# LNA.net
KiCad netlist of a schematic drawn in Altium Designer
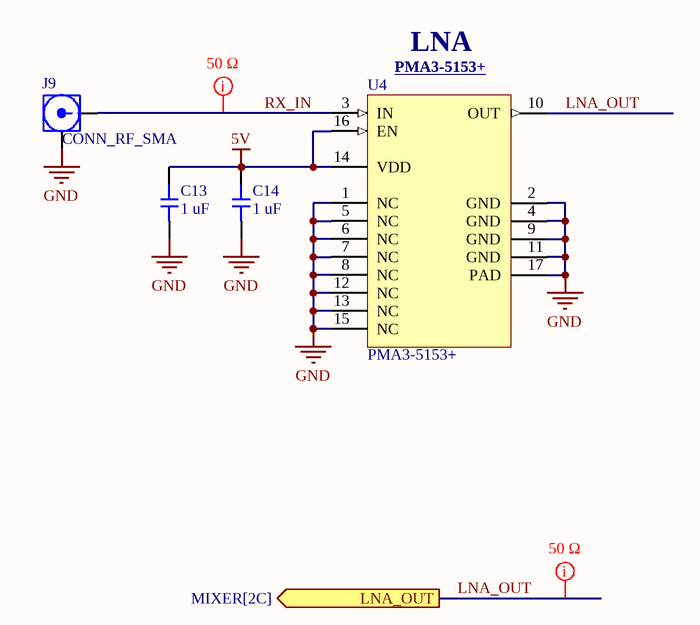
[diagram p0: LNA.SchDoc]

(export (version "E")
  (design (tool "Eeschema 10.0.6"))
  (components
    (comp (ref "C13")
      (value "1 uF")
      (footprint "CAP_0603")
      (description "25V 1uF X7R ±10% 0603 Multilayer Ceramic Capacitors MLCC - SMD/SMT ROHS")
      (fields
        (field (name "MANUFACTURER") "Samsung Electro-Mechanics")
        (field (name "MANUFACTURER PART NUMBER") "CL10B105KA8NNNC")
      )
      (libsource (lib "Titan") (part "CAP"))
    )
    (comp (ref "C14")
      (value "1 uF")
      (footprint "CAP_0603")
      (description "25V 1uF X7R ±10% 0603 Multilayer Ceramic Capacitors MLCC - SMD/SMT ROHS")
      (fields
        (field (name "MANUFACTURER") "Samsung Electro-Mechanics")
        (field (name "MANUFACTURER PART NUMBER") "CL10B105KA8NNNC")
      )
      (libsource (lib "Titan") (part "CAP"))
    )
    (comp (ref "J9")
      (value "CONN_RF_SMA")
      (footprint "142-0701-801")
      (description "RF / Coaxial Connector, SMA Coaxial, Straight Jack, Solder, 50 ohm, Beryllium Copper")
      (fields
        (field (name "MANUFACTURER") "Cinch Connectivity Solutions Johnson")
        (field (name "MANUFACTURER PART NUMBER") "142-0701-801")
      )
      (libsource (lib "Titan") (part "CONN_RF_SMA"))
    )
    (comp (ref "U4")
      (value "PMA3-5153+")
      (footprint "DQ3005")
      (description "SMT Lna, 5.5-15.5 Ghz, 50")
      (fields (field (name "MANUFACTURER") "Mini-Circuits"))
      (libsource (lib "Titan") (part "PMA3-5153+"))
    )
  )
  (nets
    (net (code "1") (name "/LNA_OUT") (class "Default")
      (node (ref "U4") (pin "10") (pinfunction "OUT_10") (pintype "output"))
    )
    (net (code "2") (name "/RX_IN") (class "Default")
      (node (ref "J9") (pin "1") (pintype "passive"))
      (node (ref "U4") (pin "3") (pinfunction "IN_3") (pintype "input"))
    )
    (net (code "3") (name "5V") (class "Default")
      (node (ref "C13") (pin "2") (pintype "passive"))
      (node (ref "C14") (pin "2") (pintype "passive"))
      (node (ref "U4") (pin "14") (pinfunction "VDD_14") (pintype "power_in"))
      (node (ref "U4") (pin "16") (pinfunction "EN_16") (pintype "input"))
    )
    (net (code "4") (name "GND") (class "Default")
      (node (ref "C13") (pin "1") (pintype "passive"))
      (node (ref "C14") (pin "1") (pintype "passive"))
      (node (ref "J9") (pin "2") (pintype "passive"))
      (node (ref "U4") (pin "1") (pinfunction "NC_1") (pintype "passive"))
      (node (ref "U4") (pin "11") (pinfunction "GND_11") (pintype "power_in"))
      (node (ref "U4") (pin "12") (pinfunction "NC_12") (pintype "passive"))
      (node (ref "U4") (pin "13") (pinfunction "NC_13") (pintype "passive"))
      (node (ref "U4") (pin "15") (pinfunction "NC_15") (pintype "passive"))
      (node (ref "U4") (pin "17") (pinfunction "PAD_17") (pintype "passive"))
      (node (ref "U4") (pin "2") (pinfunction "GND_2") (pintype "power_in"))
      (node (ref "U4") (pin "4") (pinfunction "GND_4") (pintype "power_in"))
      (node (ref "U4") (pin "5") (pinfunction "NC_5") (pintype "passive"))
      (node (ref "U4") (pin "6") (pinfunction "NC_6") (pintype "passive"))
      (node (ref "U4") (pin "7") (pinfunction "NC_7") (pintype "passive"))
      (node (ref "U4") (pin "8") (pinfunction "NC_8") (pintype "passive"))
      (node (ref "U4") (pin "9") (pinfunction "GND_9") (pintype "power_in"))
    )
  )
)
